# Encoder_Fin_ARM_-_System.net
KiCad netlist of a schematic drawn in Altium Designer
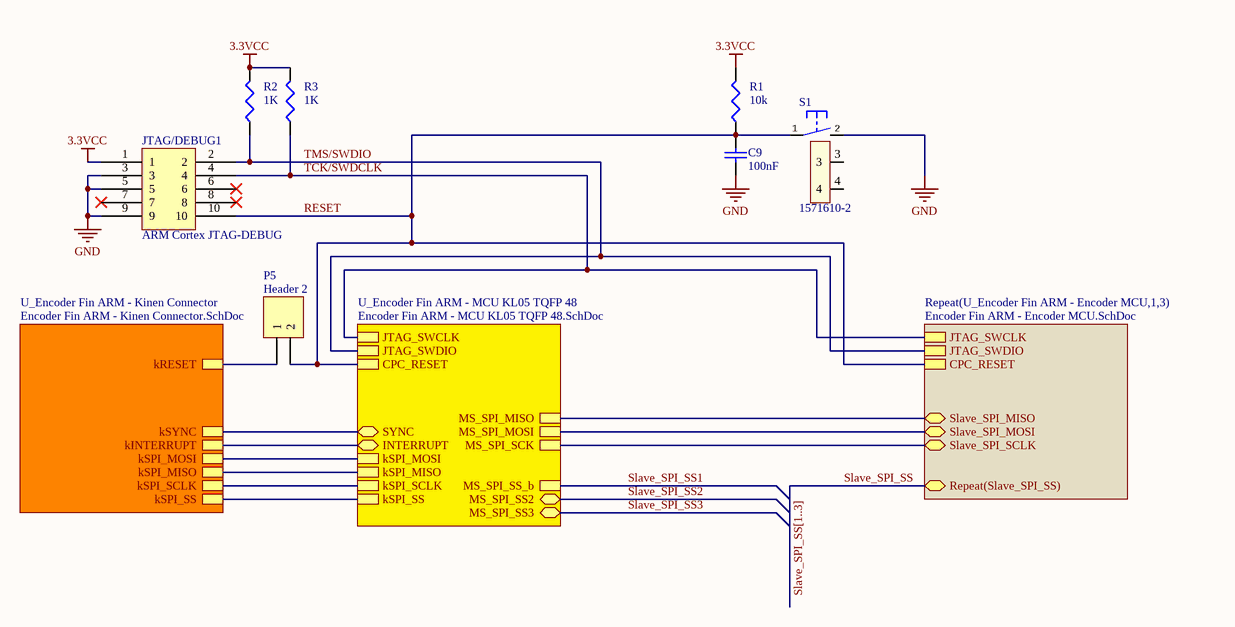
[diagram p0: Encoder Fin ARM - System.SchDoc]

(export (version "E")
  (design (tool "Eeschema 10.0.6"))
  (components
    (comp (ref "C9")
      (value "100nF")
      (footprint "1608[0603]")
      (description "Capacitor (Semiconductor SIM Model)")
      (fields (field (name "Comment") "Cap Semi") (field (name "PUBLISHER") "Altium Limited"))
      (libsource (lib "Miscellaneous Devices") (part "Cap Semi"))
    )
    (comp (ref "JTAG/DEBUG1")
      (value "ARM Cortex JTAG-DEBUG")
      (footprint "FTSH-105-XX-X-DV")
      (libsource (lib "Adams Altium Library") (part "ARM Cortex JTAG-DEBUG Header"))
    )
    (comp (ref "P5")
      (value "Header 2")
      (footprint "HDR1X2")
      (description "Header, 2-Pin")
      (fields (field (name "PUBLISHER") "Altium Limited"))
      (libsource (lib "Miscellaneous Connectors") (part "Header 2"))
    )
    (comp (ref "R1")
      (value "10k")
      (footprint "J1-0603")
      (description "Resistor")
      (fields (field (name "Comment") "Res3") (field (name "PUBLISHER") "Altium Limited"))
      (libsource (lib "Miscellaneous Devices") (part "Res3"))
    )
    (comp (ref "R2")
      (value "1K")
      (footprint "J1-0603")
      (description "Resistor")
      (fields (field (name "Comment") "Res3") (field (name "PUBLISHER") "Altium Limited"))
      (libsource (lib "Miscellaneous Devices") (part "Res3"))
    )
    (comp (ref "R3")
      (value "1K")
      (footprint "J1-0603")
      (description "Resistor")
      (fields (field (name "Comment") "Res3") (field (name "PUBLISHER") "Altium Limited"))
      (libsource (lib "Miscellaneous Devices") (part "Res3"))
    )
    (comp (ref "S1")
      (value "1571610-2")
      (footprint "B3F-31XX")
      (description "SWTCH Momentary Washable")
      (fields
        (field (name "MANUFACTURER") "Omron")
        (field (name "MANUFACTURER_1") "TE")
        (field (name "PUBLISHER") "UltiMachine")
      )
      (libsource (lib "ZMBo Schematic Library") (part "1571610-2_1"))
    )
  )
  (nets
    (net (code "5") (name "/RESET") (class "Default")
      (node (ref "C9") (pin "2") (pinfunction "2_2") (pintype "passive"))
      (node (ref "JTAG/DEBUG1") (pin "10") (pinfunction "10_10") (pintype "passive"))
      (node (ref "P5") (pin "2") (pinfunction "2_2") (pintype "passive"))
      (node (ref "R1") (pin "1") (pinfunction "1_1") (pintype "passive"))
      (node (ref "S1") (pin "1") (pinfunction "P_1") (pintype "passive"))
    )
    (net (code "12") (name "/TCK{slash}SWDCLK") (class "Default")
      (node (ref "JTAG/DEBUG1") (pin "4") (pinfunction "4_4") (pintype "passive"))
      (node (ref "R3") (pin "1") (pinfunction "1_1") (pintype "passive"))
    )
    (net (code "13") (name "/TMS{slash}SWDIO") (class "Default")
      (node (ref "JTAG/DEBUG1") (pin "2") (pinfunction "2_2") (pintype "passive"))
      (node (ref "R2") (pin "1") (pinfunction "1_1") (pintype "passive"))
    )
    (net (code "14") (name "/kRESET") (class "Default")
      (node (ref "P5") (pin "1") (pinfunction "1_1") (pintype "passive"))
    )
    (net (code "19") (name "3.3VCC") (class "Default")
      (node (ref "JTAG/DEBUG1") (pin "1") (pinfunction "1_1") (pintype "passive"))
      (node (ref "R1") (pin "2") (pinfunction "2_2") (pintype "passive"))
      (node (ref "R2") (pin "2") (pinfunction "2_2") (pintype "passive"))
      (node (ref "R3") (pin "2") (pinfunction "2_2") (pintype "passive"))
    )
    (net (code "20") (name "GND") (class "Default")
      (node (ref "C9") (pin "1") (pinfunction "1_1") (pintype "passive"))
      (node (ref "JTAG/DEBUG1") (pin "3") (pinfunction "3_3") (pintype "passive"))
      (node (ref "JTAG/DEBUG1") (pin "5") (pinfunction "5_5") (pintype "passive"))
      (node (ref "JTAG/DEBUG1") (pin "9") (pinfunction "9_9") (pintype "passive"))
      (node (ref "S1") (pin "2") (pinfunction "S_2") (pintype "passive"))
    )
    (net (code "21") (name "unconnected-(JTAG/DEBUG1-Pad6)") (class "Default")
      (node (ref "JTAG/DEBUG1") (pin "6") (pinfunction "6_6") (pintype "passive+no_connect"))
    )
    (net (code "22") (name "unconnected-(JTAG/DEBUG1-Pad7)") (class "Default")
      (node (ref "JTAG/DEBUG1") (pin "7") (pinfunction "7_7") (pintype "passive+no_connect"))
    )
    (net (code "23") (name "unconnected-(JTAG/DEBUG1-Pad8)") (class "Default")
      (node (ref "JTAG/DEBUG1") (pin "8") (pinfunction "8_8") (pintype "passive+no_connect"))
    )
    (net (code "24") (name "unconnected-(S1-Pad3)") (class "Default")
      (node (ref "S1") (pin "3") (pinfunction "3_3") (pintype "power_in"))
    )
    (net (code "25") (name "unconnected-(S1-Pad4)") (class "Default")
      (node (ref "S1") (pin "4") (pinfunction "4_4") (pintype "power_in"))
    )
  )
)
